# ESP.net
KiCad netlist of a schematic drawn in Altium Designer
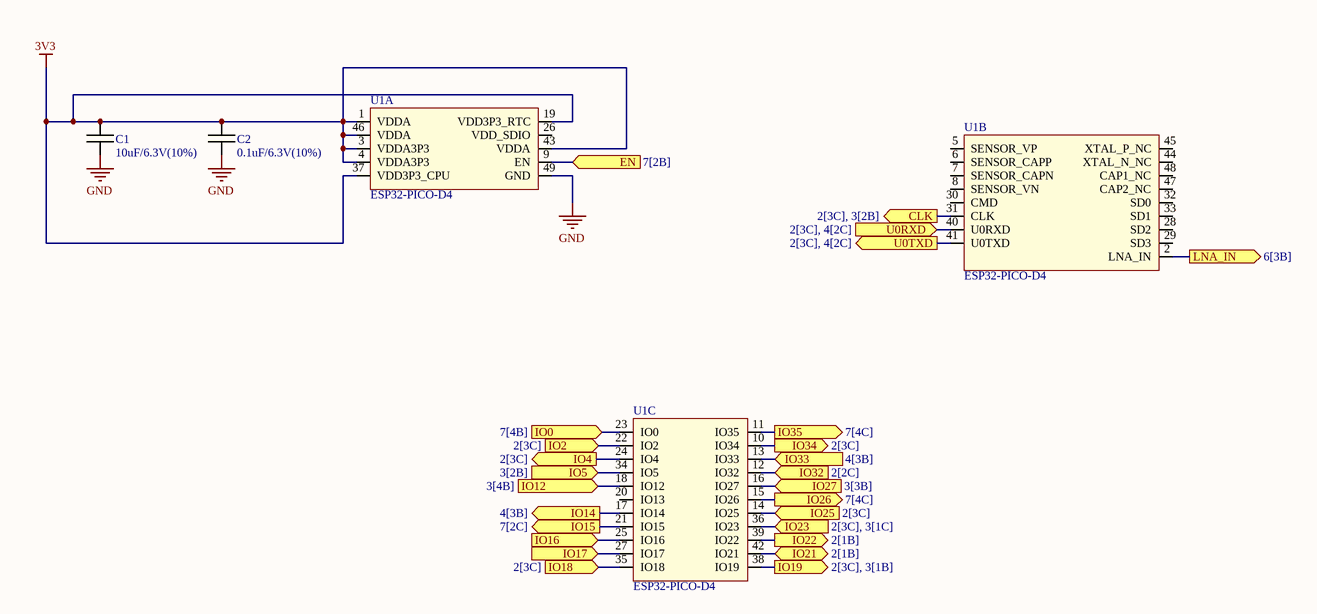
[diagram p0: ESP.SchDoc]

(export (version "E")
  (design (tool "Eeschema 10.0.6"))
  (components
    (comp (ref "C1")
      (value "10uF/6.3V(10%)")
      (footprint "CAPC1005X06N")
      (libsource (lib "SCHLibrary") (part "Capacitor"))
    )
    (comp (ref "C2")
      (value "0.1uF/6.3V(10%)")
      (footprint "CAPC1005X06N")
      (libsource (lib "SCHLibrary") (part "Capacitor"))
    )
    (comp (ref "U1")
      (value "ESP32-PICO-D4")
      (footprint "PQFN50P700X700X104_HS-49N")
      (libsource (lib "SCHLibrary") (part "ESP32"))
    )
  )
  (nets
    (net (code "1") (name "/CLK") (class "Default")
      (node (ref "U1") (pin "31") (pinfunction "CLK_31") (pintype "passive"))
    )
    (net (code "2") (name "/EN") (class "Default")
      (node (ref "U1") (pin "9") (pinfunction "EN_9") (pintype "passive"))
    )
    (net (code "3") (name "/IO0") (class "Default")
      (node (ref "U1") (pin "23") (pinfunction "IO0_23") (pintype "passive"))
    )
    (net (code "4") (name "/IO2") (class "Default")
      (node (ref "U1") (pin "22") (pinfunction "IO2_22") (pintype "passive"))
    )
    (net (code "5") (name "/IO4") (class "Default")
      (node (ref "U1") (pin "24") (pinfunction "IO4_24") (pintype "passive"))
    )
    (net (code "6") (name "/IO5") (class "Default")
      (node (ref "U1") (pin "34") (pinfunction "IO5_34") (pintype "passive"))
    )
    (net (code "7") (name "/IO12") (class "Default")
      (node (ref "U1") (pin "18") (pinfunction "IO12_18") (pintype "passive"))
    )
    (net (code "8") (name "/IO14") (class "Default")
      (node (ref "U1") (pin "17") (pinfunction "IO14_17") (pintype "passive"))
    )
    (net (code "9") (name "/IO15") (class "Default")
      (node (ref "U1") (pin "21") (pinfunction "IO15_21") (pintype "passive"))
    )
    (net (code "10") (name "/IO16") (class "Default")
      (node (ref "U1") (pin "25") (pinfunction "IO16_25") (pintype "passive"))
    )
    (net (code "11") (name "/IO17") (class "Default")
      (node (ref "U1") (pin "27") (pinfunction "IO17_27") (pintype "passive"))
    )
    (net (code "12") (name "/IO18") (class "Default")
      (node (ref "U1") (pin "35") (pinfunction "IO18_35") (pintype "passive"))
    )
    (net (code "13") (name "/IO19") (class "Default")
      (node (ref "U1") (pin "38") (pinfunction "IO19_38") (pintype "passive"))
    )
    (net (code "14") (name "/IO21") (class "Default")
      (node (ref "U1") (pin "42") (pinfunction "IO21_42") (pintype "passive"))
    )
    (net (code "15") (name "/IO22") (class "Default")
      (node (ref "U1") (pin "39") (pinfunction "IO22_39") (pintype "passive"))
    )
    (net (code "16") (name "/IO23") (class "Default")
      (node (ref "U1") (pin "36") (pinfunction "IO23_36") (pintype "passive"))
    )
    (net (code "17") (name "/IO25") (class "Default")
      (node (ref "U1") (pin "14") (pinfunction "IO25_14") (pintype "passive"))
    )
    (net (code "18") (name "/IO26") (class "Default")
      (node (ref "U1") (pin "15") (pinfunction "IO26_15") (pintype "passive"))
    )
    (net (code "19") (name "/IO27") (class "Default")
      (node (ref "U1") (pin "16") (pinfunction "IO27_16") (pintype "passive"))
    )
    (net (code "20") (name "/IO32") (class "Default")
      (node (ref "U1") (pin "12") (pinfunction "IO32_12") (pintype "passive"))
    )
    (net (code "21") (name "/IO33") (class "Default")
      (node (ref "U1") (pin "13") (pinfunction "IO33_13") (pintype "passive"))
    )
    (net (code "22") (name "/IO34") (class "Default")
      (node (ref "U1") (pin "10") (pinfunction "IO34_10") (pintype "passive"))
    )
    (net (code "23") (name "/IO35") (class "Default")
      (node (ref "U1") (pin "11") (pinfunction "IO35_11") (pintype "passive"))
    )
    (net (code "24") (name "/LNA_IN") (class "Default")
      (node (ref "U1") (pin "2") (pinfunction "LNA_IN_2") (pintype "passive"))
    )
    (net (code "25") (name "/U0RXD") (class "Default")
      (node (ref "U1") (pin "40") (pinfunction "U0RXD_40") (pintype "passive"))
    )
    (net (code "26") (name "/U0TXD") (class "Default")
      (node (ref "U1") (pin "41") (pinfunction "U0TXD_41") (pintype "passive"))
    )
    (net (code "27") (name "3V3") (class "Default")
      (node (ref "C1") (pin "2") (pinfunction "2_2") (pintype "passive"))
      (node (ref "C2") (pin "2") (pinfunction "2_2") (pintype "passive"))
      (node (ref "U1") (pin "1") (pinfunction "VDDA_1") (pintype "passive"))
      (node (ref "U1") (pin "19") (pinfunction "VDD3P3_RTC_19") (pintype "passive"))
      (node (ref "U1") (pin "3") (pinfunction "VDDA3P3_3") (pintype "passive"))
      (node (ref "U1") (pin "37") (pinfunction "VDD3P3_CPU_37") (pintype "passive"))
      (node (ref "U1") (pin "4") (pinfunction "VDDA3P3_4") (pintype "passive"))
      (node (ref "U1") (pin "43") (pinfunction "VDDA_43") (pintype "passive"))
      (node (ref "U1") (pin "46") (pinfunction "VDDA_46") (pintype "passive"))
    )
    (net (code "28") (name "GND") (class "Default")
      (node (ref "C1") (pin "1") (pinfunction "1_1") (pintype "passive"))
      (node (ref "C2") (pin "1") (pinfunction "1_1") (pintype "passive"))
      (node (ref "U1") (pin "49") (pinfunction "GND_49") (pintype "passive"))
    )
    (net (code "29") (name "unconnected-(U1A-VDD_SDIO-Pad26)") (class "Default")
      (node (ref "U1") (pin "26") (pinfunction "VDD_SDIO_26") (pintype "passive"))
    )
    (net (code "30") (name "unconnected-(U1B-CAP1_NC-Pad48)") (class "Default")
      (node (ref "U1") (pin "48") (pinfunction "CAP1_NC_48") (pintype "passive"))
    )
    (net (code "31") (name "unconnected-(U1B-CAP2_NC-Pad47)") (class "Default")
      (node (ref "U1") (pin "47") (pinfunction "CAP2_NC_47") (pintype "passive"))
    )
    (net (code "32") (name "unconnected-(U1B-CMD-Pad30)") (class "Default")
      (node (ref "U1") (pin "30") (pinfunction "CMD_30") (pintype "passive"))
    )
    (net (code "33") (name "unconnected-(U1B-SD0-Pad32)") (class "Default")
      (node (ref "U1") (pin "32") (pinfunction "SD0_32") (pintype "passive"))
    )
    (net (code "34") (name "unconnected-(U1B-SD1-Pad33)") (class "Default")
      (node (ref "U1") (pin "33") (pinfunction "SD1_33") (pintype "passive"))
    )
    (net (code "35") (name "unconnected-(U1B-SD2-Pad28)") (class "Default")
      (node (ref "U1") (pin "28") (pinfunction "SD2_28") (pintype "passive"))
    )
    (net (code "36") (name "unconnected-(U1B-SD3-Pad29)") (class "Default")
      (node (ref "U1") (pin "29") (pinfunction "SD3_29") (pintype "passive"))
    )
    (net (code "37") (name "unconnected-(U1B-SENSOR_CAPN-Pad7)") (class "Default")
      (node (ref "U1") (pin "7") (pinfunction "SENSOR_CAPN_7") (pintype "passive"))
    )
    (net (code "38") (name "unconnected-(U1B-SENSOR_CAPP-Pad6)") (class "Default")
      (node (ref "U1") (pin "6") (pinfunction "SENSOR_CAPP_6") (pintype "passive"))
    )
    (net (code "39") (name "unconnected-(U1B-SENSOR_VN-Pad8)") (class "Default")
      (node (ref "U1") (pin "8") (pinfunction "SENSOR_VN_8") (pintype "passive"))
    )
    (net (code "40") (name "unconnected-(U1B-SENSOR_VP-Pad5)") (class "Default")
      (node (ref "U1") (pin "5") (pinfunction "SENSOR_VP_5") (pintype "passive"))
    )
    (net (code "41") (name "unconnected-(U1B-XTAL_N_NC-Pad44)") (class "Default")
      (node (ref "U1") (pin "44") (pinfunction "XTAL_N_NC_44") (pintype "passive"))
    )
    (net (code "42") (name "unconnected-(U1B-XTAL_P_NC-Pad45)") (class "Default")
      (node (ref "U1") (pin "45") (pinfunction "XTAL_P_NC_45") (pintype "passive"))
    )
    (net (code "43") (name "unconnected-(U1C-IO13-Pad20)") (class "Default")
      (node (ref "U1") (pin "20") (pinfunction "IO13_20") (pintype "passive"))
    )
  )
)
